# W7IUV_preamp.net
KiCad netlist of a schematic drawn in EAGLE
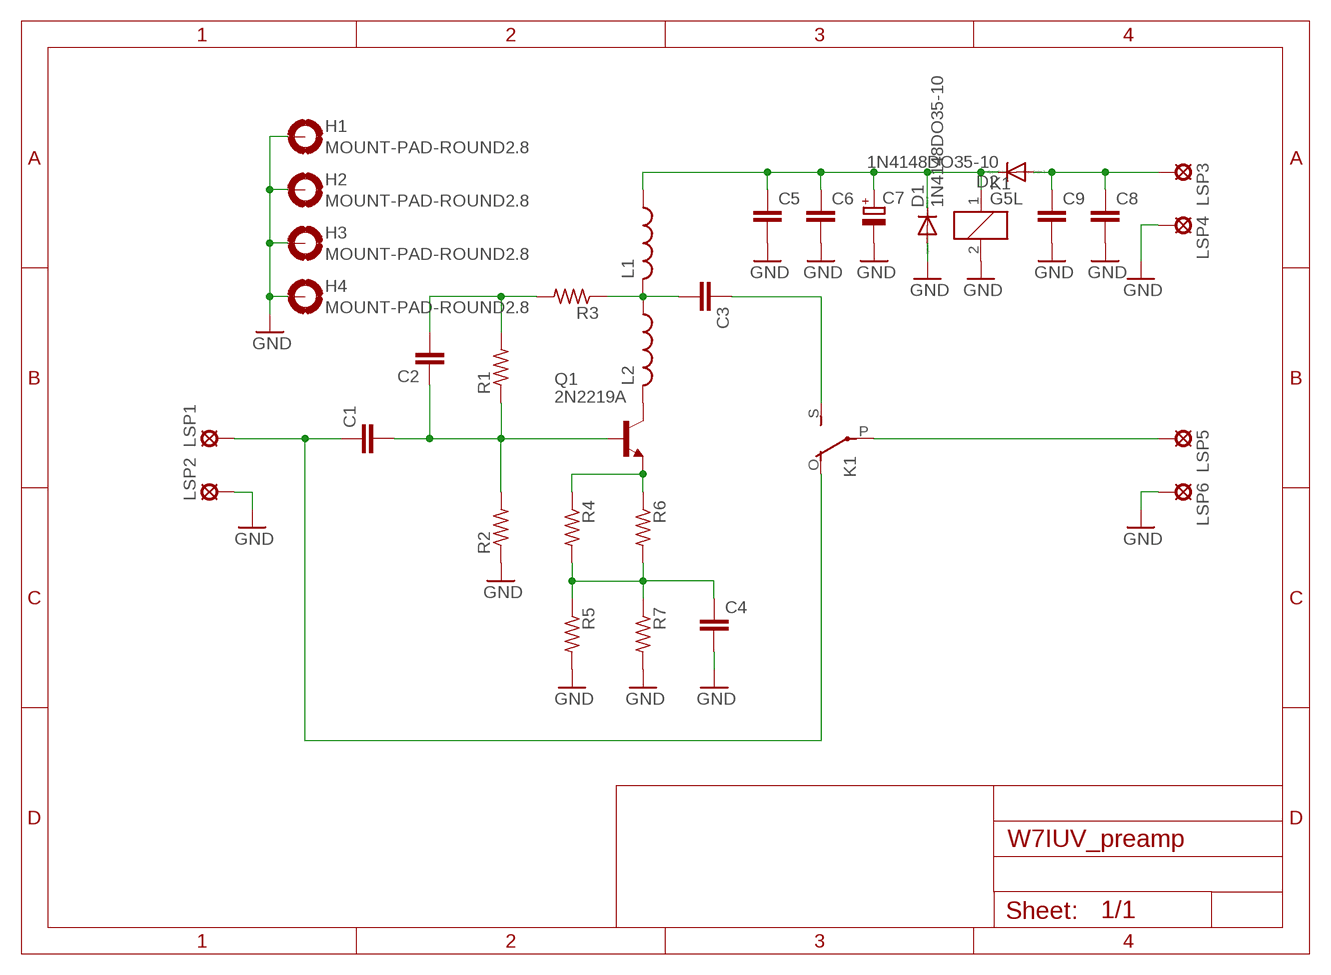
[diagram p0: schematic, sheet 1]

(export (version "E")
  (design (tool "Eeschema 10.0.6"))
  (components
    (comp (ref "C1")
      (value "C-EUC1206")
      (footprint "eagle-import:C1206")
      (libsource (lib "eagle-import") (part "C-EUC1206"))
    )
    (comp (ref "C2")
      (value "C-EUC1206")
      (footprint "eagle-import:C1206")
      (libsource (lib "eagle-import") (part "C-EUC1206"))
    )
    (comp (ref "C3")
      (value "C-EUC1206")
      (footprint "eagle-import:C1206")
      (libsource (lib "eagle-import") (part "C-EUC1206"))
    )
    (comp (ref "C4")
      (value "C-EUC1206")
      (footprint "eagle-import:C1206")
      (libsource (lib "eagle-import") (part "C-EUC1206"))
    )
    (comp (ref "C5")
      (value "C-EUC1206")
      (footprint "eagle-import:C1206")
      (libsource (lib "eagle-import") (part "C-EUC1206"))
    )
    (comp (ref "C6")
      (value "C-EUC1206")
      (footprint "eagle-import:C1206")
      (libsource (lib "eagle-import") (part "C-EUC1206"))
    )
    (comp (ref "C7")
      (value "CPOL-EUE5-10.5")
      (footprint "eagle-import:E5-10,5")
      (libsource (lib "eagle-import") (part "CPOL-EUE5-10.5"))
    )
    (comp (ref "C8")
      (value "C-EUC1206")
      (footprint "eagle-import:C1206")
      (libsource (lib "eagle-import") (part "C-EUC1206"))
    )
    (comp (ref "C9")
      (value "C-EUC1206")
      (footprint "eagle-import:C1206")
      (libsource (lib "eagle-import") (part "C-EUC1206"))
    )
    (comp (ref "D1")
      (value "1N4148DO35-10")
      (footprint "eagle-import:DO35-10")
      (libsource (lib "eagle-import") (part "1N4148DO35-10"))
    )
    (comp (ref "D2")
      (value "1N4148DO35-10")
      (footprint "eagle-import:DO35-10")
      (libsource (lib "eagle-import") (part "1N4148DO35-10"))
    )
    (comp (ref "H1")
      (value "MOUNT-PAD-ROUND2.8")
      (footprint "eagle-import:2,8-PAD")
      (libsource (lib "eagle-import") (part "MOUNT-PAD-ROUND2.8"))
    )
    (comp (ref "H2")
      (value "MOUNT-PAD-ROUND2.8")
      (footprint "eagle-import:2,8-PAD")
      (libsource (lib "eagle-import") (part "MOUNT-PAD-ROUND2.8"))
    )
    (comp (ref "H3")
      (value "MOUNT-PAD-ROUND2.8")
      (footprint "eagle-import:2,8-PAD")
      (libsource (lib "eagle-import") (part "MOUNT-PAD-ROUND2.8"))
    )
    (comp (ref "H4")
      (value "MOUNT-PAD-ROUND2.8")
      (footprint "eagle-import:2,8-PAD")
      (libsource (lib "eagle-import") (part "MOUNT-PAD-ROUND2.8"))
    )
    (comp (ref "K1")
      (value "G5L")
      (footprint "eagle-import:G5LE")
      (libsource (lib "eagle-import") (part "G5L"))
    )
    (comp (ref "L1")
      (value "L-USLAN02KR")
      (footprint "eagle-import:LAN02KR")
      (libsource (lib "eagle-import") (part "L-USLAN02KR"))
    )
    (comp (ref "L2")
      (value "L-USLAN02KR")
      (footprint "eagle-import:LAN02KR")
      (libsource (lib "eagle-import") (part "L-USLAN02KR"))
    )
    (comp (ref "LSP1")
      (value "MCS08")
      (footprint "eagle-import:MCS08")
      (libsource (lib "eagle-import") (part "MCS08"))
    )
    (comp (ref "LSP2")
      (value "MCS08")
      (footprint "eagle-import:MCS08")
      (libsource (lib "eagle-import") (part "MCS08"))
    )
    (comp (ref "LSP3")
      (value "MCS08")
      (footprint "eagle-import:MCS08")
      (libsource (lib "eagle-import") (part "MCS08"))
    )
    (comp (ref "LSP4")
      (value "MCS08")
      (footprint "eagle-import:MCS08")
      (libsource (lib "eagle-import") (part "MCS08"))
    )
    (comp (ref "LSP5")
      (value "MCS08")
      (footprint "eagle-import:MCS08")
      (libsource (lib "eagle-import") (part "MCS08"))
    )
    (comp (ref "LSP6")
      (value "MCS08")
      (footprint "eagle-import:MCS08")
      (libsource (lib "eagle-import") (part "MCS08"))
    )
    (comp (ref "Q1")
      (value "2N2219A")
      (footprint "eagle-import:TO39")
      (libsource (lib "eagle-import") (part "2N2219A"))
    )
    (comp (ref "R1")
      (value "R-US_M1206")
      (footprint "eagle-import:M1206")
      (libsource (lib "eagle-import") (part "R-US_M1206"))
    )
    (comp (ref "R2")
      (value "R-US_M1206")
      (footprint "eagle-import:M1206")
      (libsource (lib "eagle-import") (part "R-US_M1206"))
    )
    (comp (ref "R3")
      (value "R-US_M1206")
      (footprint "eagle-import:M1206")
      (libsource (lib "eagle-import") (part "R-US_M1206"))
    )
    (comp (ref "R4")
      (value "R-US_M1206")
      (footprint "eagle-import:M1206")
      (libsource (lib "eagle-import") (part "R-US_M1206"))
    )
    (comp (ref "R5")
      (value "R-US_M1206")
      (footprint "eagle-import:M1206")
      (libsource (lib "eagle-import") (part "R-US_M1206"))
    )
    (comp (ref "R6")
      (value "R-US_M1206")
      (footprint "eagle-import:M1206")
      (libsource (lib "eagle-import") (part "R-US_M1206"))
    )
    (comp (ref "R7")
      (value "R-US_M1206")
      (footprint "eagle-import:M1206")
      (libsource (lib "eagle-import") (part "R-US_M1206"))
    )
  )
  (nets
    (net (code "1") (name "GND") (class "Default")
      (node (ref "C4") (pin "2") (pinfunction "2_2") (pintype "passive"))
      (node (ref "C5") (pin "2") (pinfunction "2_2") (pintype "passive"))
      (node (ref "C6") (pin "2") (pinfunction "2_2") (pintype "passive"))
      (node (ref "C7") (pin "-") (pinfunction "-_-") (pintype "passive"))
      (node (ref "C8") (pin "2") (pinfunction "2_2") (pintype "passive"))
      (node (ref "C9") (pin "2") (pinfunction "2_2") (pintype "passive"))
      (node (ref "D1") (pin "A") (pinfunction "A_A") (pintype "passive"))
      (node (ref "H1") (pin "B2,8") (pinfunction "MOUNT_B2,8") (pintype "passive"))
      (node (ref "H2") (pin "B2,8") (pinfunction "MOUNT_B2,8") (pintype "passive"))
      (node (ref "H3") (pin "B2,8") (pinfunction "MOUNT_B2,8") (pintype "passive"))
      (node (ref "H4") (pin "B2,8") (pinfunction "MOUNT_B2,8") (pintype "passive"))
      (node (ref "K1") (pin "2") (pinfunction "2_2") (pintype "passive"))
      (node (ref "LSP2") (pin "MP") (pinfunction "MP_MP") (pintype "passive"))
      (node (ref "LSP4") (pin "MP") (pinfunction "MP_MP") (pintype "passive"))
      (node (ref "LSP6") (pin "MP") (pinfunction "MP_MP") (pintype "passive"))
      (node (ref "R2") (pin "1") (pinfunction "1_1") (pintype "passive"))
      (node (ref "R5") (pin "2") (pinfunction "2_2") (pintype "passive"))
      (node (ref "R7") (pin "2") (pinfunction "2_2") (pintype "passive"))
    )
    (net (code "2") (name "Net-(C1-Pad1)") (class "Default")
      (node (ref "C1") (pin "1") (pinfunction "1_1") (pintype "passive"))
      (node (ref "K1") (pin "O") (pinfunction "O_O") (pintype "passive"))
      (node (ref "LSP1") (pin "MP") (pinfunction "MP_MP") (pintype "passive"))
    )
    (net (code "3") (name "Net-(C2-Pad2)") (class "Default")
      (node (ref "C2") (pin "2") (pinfunction "2_2") (pintype "passive"))
      (node (ref "R1") (pin "2") (pinfunction "2_2") (pintype "passive"))
      (node (ref "R3") (pin "2") (pinfunction "2_2") (pintype "passive"))
    )
    (net (code "4") (name "Net-(C3-Pad1)") (class "Default")
      (node (ref "C3") (pin "1") (pinfunction "1_1") (pintype "passive"))
      (node (ref "K1") (pin "S") (pinfunction "S_S") (pintype "passive"))
    )
    (net (code "5") (name "Net-(C3-Pad2)") (class "Default")
      (node (ref "C3") (pin "2") (pinfunction "2_2") (pintype "passive"))
      (node (ref "L1") (pin "2") (pinfunction "2_2") (pintype "passive"))
      (node (ref "L2") (pin "1") (pinfunction "1_1") (pintype "passive"))
      (node (ref "R3") (pin "1") (pinfunction "1_1") (pintype "passive"))
    )
    (net (code "6") (name "Net-(C4-Pad1)") (class "Default")
      (node (ref "C4") (pin "1") (pinfunction "1_1") (pintype "passive"))
      (node (ref "R4") (pin "2") (pinfunction "2_2") (pintype "passive"))
      (node (ref "R5") (pin "1") (pinfunction "1_1") (pintype "passive"))
      (node (ref "R6") (pin "2") (pinfunction "2_2") (pintype "passive"))
      (node (ref "R7") (pin "1") (pinfunction "1_1") (pintype "passive"))
    )
    (net (code "7") (name "Net-(C5-Pad1)") (class "Default")
      (node (ref "C5") (pin "1") (pinfunction "1_1") (pintype "passive"))
      (node (ref "C6") (pin "1") (pinfunction "1_1") (pintype "passive"))
      (node (ref "C7") (pin "+") (pinfunction "+_+") (pintype "passive"))
      (node (ref "D1") (pin "C") (pinfunction "C_C") (pintype "passive"))
      (node (ref "D2") (pin "C") (pinfunction "C_C") (pintype "passive"))
      (node (ref "K1") (pin "1") (pinfunction "1_1") (pintype "passive"))
      (node (ref "L1") (pin "1") (pinfunction "1_1") (pintype "passive"))
    )
    (net (code "8") (name "Net-(C8-Pad1)") (class "Default")
      (node (ref "C8") (pin "1") (pinfunction "1_1") (pintype "passive"))
      (node (ref "C9") (pin "1") (pinfunction "1_1") (pintype "passive"))
      (node (ref "D2") (pin "A") (pinfunction "A_A") (pintype "passive"))
      (node (ref "LSP3") (pin "MP") (pinfunction "MP_MP") (pintype "passive"))
    )
    (net (code "9") (name "Net-(K1-PadP)") (class "Default")
      (node (ref "K1") (pin "P") (pinfunction "P_P") (pintype "passive"))
      (node (ref "LSP5") (pin "MP") (pinfunction "MP_MP") (pintype "passive"))
    )
    (net (code "10") (name "Net-(Q1-B)") (class "Default")
      (node (ref "C1") (pin "2") (pinfunction "2_2") (pintype "passive"))
      (node (ref "C2") (pin "1") (pinfunction "1_1") (pintype "passive"))
      (node (ref "Q1") (pin "2") (pinfunction "B_2") (pintype "passive"))
      (node (ref "R1") (pin "1") (pinfunction "1_1") (pintype "passive"))
      (node (ref "R2") (pin "2") (pinfunction "2_2") (pintype "passive"))
    )
    (net (code "11") (name "Net-(Q1-C)") (class "Default")
      (node (ref "L2") (pin "2") (pinfunction "2_2") (pintype "passive"))
      (node (ref "Q1") (pin "3") (pinfunction "C_3") (pintype "passive"))
    )
    (net (code "12") (name "Net-(Q1-E)") (class "Default")
      (node (ref "Q1") (pin "1") (pinfunction "E_1") (pintype "passive"))
      (node (ref "R4") (pin "1") (pinfunction "1_1") (pintype "passive"))
      (node (ref "R6") (pin "1") (pinfunction "1_1") (pintype "passive"))
    )
  )
)
